# AT90PWM_PCB_Diff.net
KiCad netlist of a schematic drawn in Altium Designer
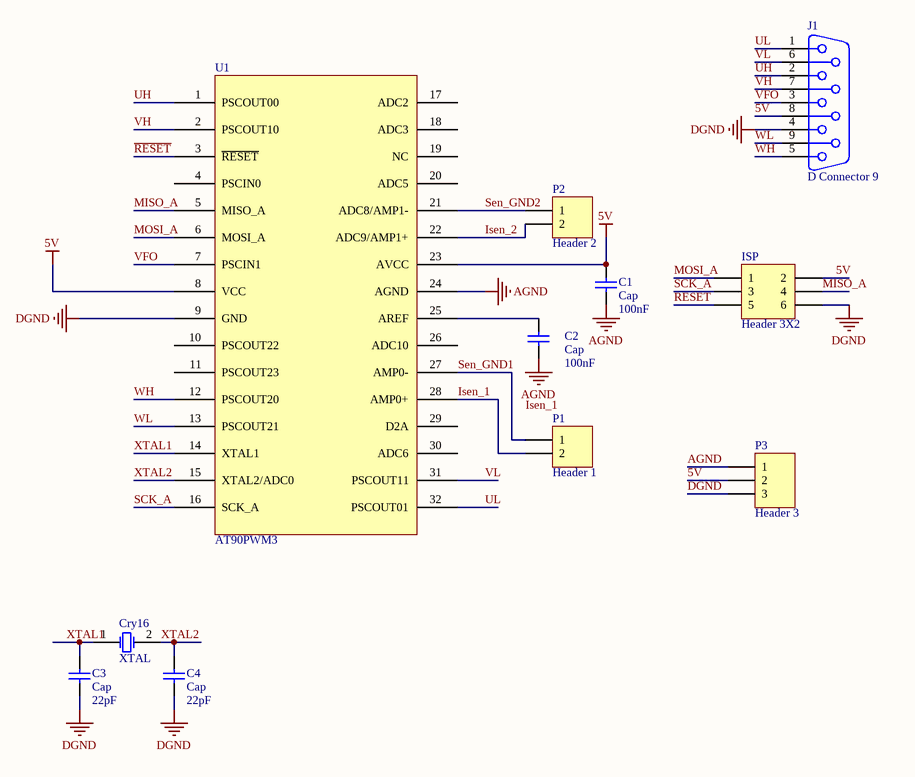
[diagram p0: AT90PWM_PCB_Diff.SchDoc]

(export (version "E")
  (design (tool "Eeschema 10.0.6"))
  (components
    (comp (ref "C1")
      (value "Cap")
      (footprint "NPolar_Cap")
      (description "Capacitor")
      (fields (field (name "ALTIUM_VALUE") "100nF") (field (name "PUBLISHER") "Altium Limited"))
      (libsource (lib "Miscellaneous Devices") (part "Cap"))
    )
    (comp (ref "C2")
      (value "Cap")
      (footprint "NPolar_Cap")
      (description "Capacitor")
      (fields (field (name "ALTIUM_VALUE") "100nF") (field (name "PUBLISHER") "Altium Limited"))
      (libsource (lib "Miscellaneous Devices") (part "Cap"))
    )
    (comp (ref "C3")
      (value "Cap")
      (footprint "NPolar_Cap")
      (description "Capacitor")
      (fields (field (name "ALTIUM_VALUE") "22pF") (field (name "PUBLISHER") "Altium Limited"))
      (libsource (lib "Miscellaneous Devices") (part "Cap"))
    )
    (comp (ref "C4")
      (value "Cap")
      (footprint "NPolar_Cap")
      (description "Capacitor")
      (fields (field (name "ALTIUM_VALUE") "22pF") (field (name "PUBLISHER") "Altium Limited"))
      (libsource (lib "Miscellaneous Devices") (part "Cap"))
    )
    (comp (ref "Cry16")
      (value "XTAL")
      (footprint "16MHz Crystal")
      (description "Crystal Oscillator")
      (fields (field (name "PUBLISHER") "Altium Limited"))
      (libsource (lib "Miscellaneous Devices") (part "XTAL"))
    )
    (comp (ref "ISP")
      (value "Header 3X2")
      (footprint "HDR2X3")
      (description "Header, 3-Pin, Dual row")
      (fields (field (name "PUBLISHER") "Altium Limited"))
      (libsource (lib "Miscellaneous Connectors") (part "Header 3X2"))
    )
    (comp (ref "J1")
      (value "D Connector 9")
      (footprint "DSUB1.385-2H9")
      (description "Receptacle Assembly, 9 Position, Right Angle")
      (fields (field (name "PUBLISHER") "Altium Limited"))
      (libsource (lib "MyBoard_v1") (part "D Connector 9"))
    )
    (comp (ref "P1")
      (value "Header 1")
      (footprint "HDR1X2")
      (description "Header, 2-Pin")
      (fields (field (name "PUBLISHER") "Altium Limited"))
      (libsource (lib "Miscellaneous Connectors") (part "Header 2"))
    )
    (comp (ref "P2")
      (value "Header 2")
      (footprint "HDR1X2")
      (description "Header, 2-Pin")
      (fields (field (name "PUBLISHER") "Altium Limited"))
      (libsource (lib "Miscellaneous Connectors") (part "Header 2"))
    )
    (comp (ref "P3")
      (value "Header 3")
      (footprint "HDR1X3")
      (description "Header, 3-Pin")
      (fields (field (name "PUBLISHER") "Altium Limited"))
      (libsource (lib "Miscellaneous Connectors") (part "Header 3"))
    )
    (comp (ref "U1")
      (value "AT90PWM3")
      (footprint "FYP:AT90PWM3B")
      (libsource (lib "MyBoard_v1") (part "AT90PWM3"))
    )
  )
  (nets
    (net (code "1") (name "/Isen_1") (class "Default")
      (node (ref "P1") (pin "2") (pinfunction "2_2") (pintype "passive"))
      (node (ref "U1") (pin "28") (pinfunction "AMP0+_28") (pintype "passive"))
    )
    (net (code "2") (name "/Isen_2") (class "Default")
      (node (ref "P2") (pin "2") (pinfunction "2_2") (pintype "passive"))
      (node (ref "U1") (pin "22") (pinfunction "ADC9/AMP1+_22") (pintype "passive"))
    )
    (net (code "3") (name "/MISO_A") (class "Default")
      (node (ref "ISP") (pin "4") (pinfunction "4_4") (pintype "passive"))
      (node (ref "U1") (pin "5") (pinfunction "MISO_A_5") (pintype "passive"))
    )
    (net (code "4") (name "/MOSI_A") (class "Default")
      (node (ref "ISP") (pin "1") (pinfunction "1_1") (pintype "passive"))
      (node (ref "U1") (pin "6") (pinfunction "MOSI_A_6") (pintype "passive"))
    )
    (net (code "5") (name "/SCK_A") (class "Default")
      (node (ref "ISP") (pin "3") (pinfunction "3_3") (pintype "passive"))
      (node (ref "U1") (pin "16") (pinfunction "SCK_A_16") (pintype "passive"))
    )
    (net (code "6") (name "/Sen_GND1") (class "Default")
      (node (ref "P1") (pin "1") (pinfunction "1_1") (pintype "passive"))
      (node (ref "U1") (pin "27") (pinfunction "AMP0-_27") (pintype "passive"))
    )
    (net (code "7") (name "/Sen_GND2") (class "Default")
      (node (ref "P2") (pin "1") (pinfunction "1_1") (pintype "passive"))
      (node (ref "U1") (pin "21") (pinfunction "ADC8/AMP1-_21") (pintype "passive"))
    )
    (net (code "8") (name "/UH") (class "Default")
      (node (ref "J1") (pin "2") (pinfunction "2_2") (pintype "passive"))
      (node (ref "U1") (pin "1") (pinfunction "PSCOUT00_1") (pintype "passive"))
    )
    (net (code "9") (name "/UL") (class "Default")
      (node (ref "J1") (pin "1") (pinfunction "1_1") (pintype "passive"))
      (node (ref "U1") (pin "32") (pinfunction "PSCOUT01_32") (pintype "passive"))
    )
    (net (code "10") (name "/VFO") (class "Default")
      (node (ref "J1") (pin "3") (pinfunction "3_3") (pintype "passive"))
      (node (ref "U1") (pin "7") (pinfunction "PSCIN1_7") (pintype "passive"))
    )
    (net (code "11") (name "/VH") (class "Default")
      (node (ref "J1") (pin "7") (pinfunction "7_7") (pintype "passive"))
      (node (ref "U1") (pin "2") (pinfunction "PSCOUT10_2") (pintype "passive"))
    )
    (net (code "12") (name "/VL") (class "Default")
      (node (ref "J1") (pin "6") (pinfunction "6_6") (pintype "passive"))
      (node (ref "U1") (pin "31") (pinfunction "PSCOUT11_31") (pintype "passive"))
    )
    (net (code "13") (name "/WH") (class "Default")
      (node (ref "J1") (pin "5") (pinfunction "5_5") (pintype "passive"))
      (node (ref "U1") (pin "12") (pinfunction "PSCOUT20_12") (pintype "passive"))
    )
    (net (code "14") (name "/WL") (class "Default")
      (node (ref "J1") (pin "9") (pinfunction "9_9") (pintype "passive"))
      (node (ref "U1") (pin "13") (pinfunction "PSCOUT21_13") (pintype "passive"))
    )
    (net (code "15") (name "/XTAL1") (class "Default")
      (node (ref "C3") (pin "2") (pinfunction "2_2") (pintype "passive"))
      (node (ref "Cry16") (pin "1") (pinfunction "OSC1_1") (pintype "passive"))
      (node (ref "U1") (pin "14") (pinfunction "XTAL1_14") (pintype "passive"))
    )
    (net (code "16") (name "/XTAL2") (class "Default")
      (node (ref "C4") (pin "2") (pinfunction "2_2") (pintype "passive"))
      (node (ref "Cry16") (pin "2") (pinfunction "OSC2_2") (pintype "passive"))
      (node (ref "U1") (pin "15") (pinfunction "XTAL2/ADC0_15") (pintype "passive"))
    )
    (net (code "17") (name "/~{RESET}") (class "Default")
      (node (ref "ISP") (pin "5") (pinfunction "5_5") (pintype "passive"))
      (node (ref "U1") (pin "3") (pinfunction "~{RESET}_3") (pintype "passive"))
    )
    (net (code "18") (name "5V") (class "Default")
      (node (ref "C1") (pin "2") (pinfunction "2_2") (pintype "passive"))
      (node (ref "ISP") (pin "2") (pinfunction "2_2") (pintype "passive"))
      (node (ref "J1") (pin "8") (pinfunction "8_8") (pintype "passive"))
      (node (ref "P3") (pin "2") (pinfunction "2_2") (pintype "passive"))
      (node (ref "U1") (pin "23") (pinfunction "AVCC_23") (pintype "passive"))
      (node (ref "U1") (pin "8") (pinfunction "VCC_8") (pintype "passive"))
    )
    (net (code "19") (name "AGND") (class "Default")
      (node (ref "C1") (pin "1") (pinfunction "1_1") (pintype "passive"))
      (node (ref "C2") (pin "1") (pinfunction "1_1") (pintype "passive"))
      (node (ref "P3") (pin "1") (pinfunction "1_1") (pintype "passive"))
      (node (ref "U1") (pin "24") (pinfunction "AGND_24") (pintype "passive"))
    )
    (net (code "20") (name "DGND") (class "Default")
      (node (ref "C3") (pin "1") (pinfunction "1_1") (pintype "passive"))
      (node (ref "C4") (pin "1") (pinfunction "1_1") (pintype "passive"))
      (node (ref "ISP") (pin "6") (pinfunction "6_6") (pintype "passive"))
      (node (ref "J1") (pin "4") (pinfunction "4_4") (pintype "passive"))
      (node (ref "P3") (pin "3") (pinfunction "3_3") (pintype "passive"))
      (node (ref "U1") (pin "9") (pinfunction "GND_9") (pintype "passive"))
    )
    (net (code "21") (name "Net-(U1-AREF)") (class "Default")
      (node (ref "C2") (pin "2") (pinfunction "2_2") (pintype "passive"))
      (node (ref "U1") (pin "25") (pinfunction "AREF_25") (pintype "passive"))
    )
    (net (code "22") (name "unconnected-(U1-ADC2-Pad17)") (class "Default")
      (node (ref "U1") (pin "17") (pinfunction "ADC2_17") (pintype "passive"))
    )
    (net (code "23") (name "unconnected-(U1-ADC3-Pad18)") (class "Default")
      (node (ref "U1") (pin "18") (pinfunction "ADC3_18") (pintype "passive"))
    )
    (net (code "24") (name "unconnected-(U1-ADC5-Pad20)") (class "Default")
      (node (ref "U1") (pin "20") (pinfunction "ADC5_20") (pintype "passive"))
    )
    (net (code "25") (name "unconnected-(U1-ADC6-Pad30)") (class "Default")
      (node (ref "U1") (pin "30") (pinfunction "ADC6_30") (pintype "passive"))
    )
    (net (code "26") (name "unconnected-(U1-ADC10-Pad26)") (class "Default")
      (node (ref "U1") (pin "26") (pinfunction "ADC10_26") (pintype "passive"))
    )
    (net (code "27") (name "unconnected-(U1-D2A-Pad29)") (class "Default")
      (node (ref "U1") (pin "29") (pinfunction "D2A_29") (pintype "passive"))
    )
    (net (code "28") (name "unconnected-(U1-NC-Pad19)") (class "Default")
      (node (ref "U1") (pin "19") (pinfunction "NC_19") (pintype "passive"))
    )
    (net (code "29") (name "unconnected-(U1-PSCIN0-Pad4)") (class "Default")
      (node (ref "U1") (pin "4") (pinfunction "PSCIN0_4") (pintype "passive"))
    )
    (net (code "30") (name "unconnected-(U1-PSCOUT22-Pad10)") (class "Default")
      (node (ref "U1") (pin "10") (pinfunction "PSCOUT22_10") (pintype "passive"))
    )
    (net (code "31") (name "unconnected-(U1-PSCOUT23-Pad11)") (class "Default")
      (node (ref "U1") (pin "11") (pinfunction "PSCOUT23_11") (pintype "passive"))
    )
  )
)
